# SDRAM.net
KiCad netlist of a schematic drawn in Altium Designer
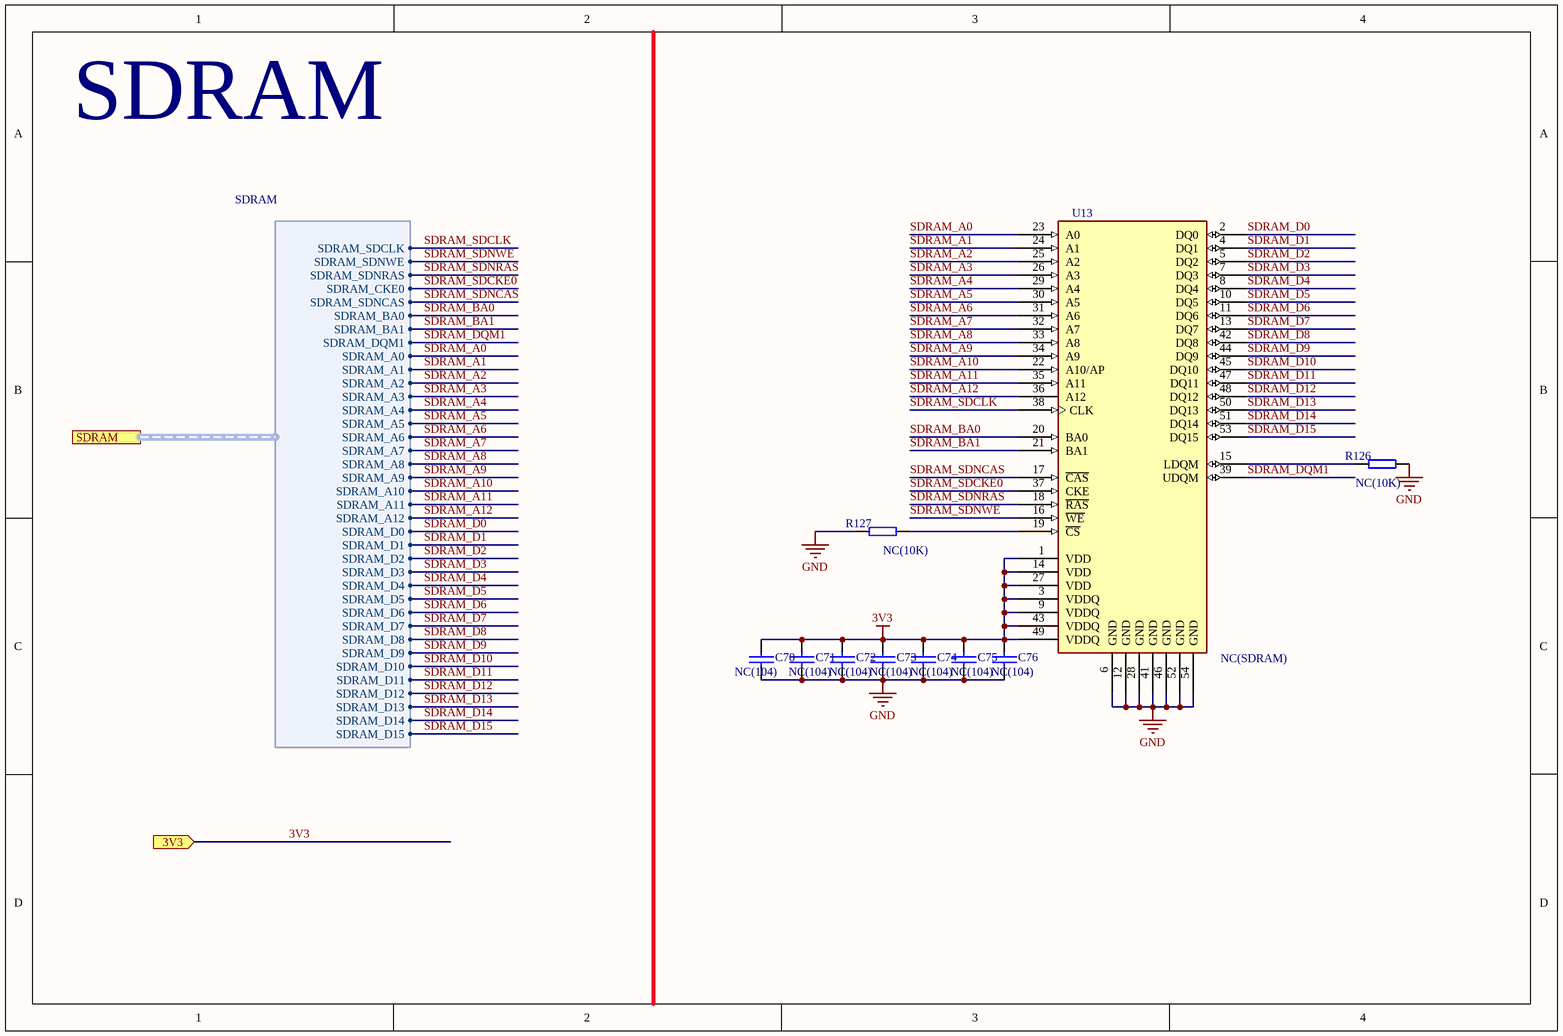
[diagram p0: SDRAM.SchDoc]

(export (version "E")
  (design (tool "Eeschema 10.0.6"))
  (components
    (comp (ref "C70")
      (value "NC(104)")
      (footprint "0402_C")
      (description "Capacitor")
      (libsource (lib "wch_sch_others") (part "CAP"))
    )
    (comp (ref "C71")
      (value "NC(104)")
      (footprint "0402_C")
      (description "Capacitor")
      (libsource (lib "wch_sch_others") (part "CAP"))
    )
    (comp (ref "C72")
      (value "NC(104)")
      (footprint "0402_C")
      (description "Capacitor")
      (libsource (lib "wch_sch_others") (part "CAP"))
    )
    (comp (ref "C73")
      (value "NC(104)")
      (footprint "0402_C")
      (description "Capacitor")
      (libsource (lib "wch_sch_others") (part "CAP"))
    )
    (comp (ref "C74")
      (value "NC(104)")
      (footprint "0402_C")
      (description "Capacitor")
      (libsource (lib "wch_sch_others") (part "CAP"))
    )
    (comp (ref "C75")
      (value "NC(104)")
      (footprint "0402_C")
      (description "Capacitor")
      (libsource (lib "wch_sch_others") (part "CAP"))
    )
    (comp (ref "C76")
      (value "NC(104)")
      (footprint "0402_C")
      (description "Capacitor")
      (libsource (lib "wch_sch_others") (part "CAP"))
    )
    (comp (ref "R126") (value "NC(10K)") (footprint "0402") (libsource (lib "*") (part "RES")))
    (comp (ref "R127") (value "NC(10K)") (footprint "0402") (libsource (lib "*") (part "RES")))
    (comp (ref "U13") (value "NC(SDRAM)") (libsource (lib "wch_sch_others") (part "W9825G6KH-6")))
  )
  (nets
    (net (code "2") (name "/SDRAM_A0") (class "Default")
      (node (ref "U13") (pin "23") (pinfunction "A0_23") (pintype "input"))
    )
    (net (code "3") (name "/SDRAM_A1") (class "Default")
      (node (ref "U13") (pin "24") (pinfunction "A1_24") (pintype "input"))
    )
    (net (code "4") (name "/SDRAM_A2") (class "Default")
      (node (ref "U13") (pin "25") (pinfunction "A2_25") (pintype "input"))
    )
    (net (code "5") (name "/SDRAM_A3") (class "Default")
      (node (ref "U13") (pin "26") (pinfunction "A3_26") (pintype "input"))
    )
    (net (code "6") (name "/SDRAM_A4") (class "Default")
      (node (ref "U13") (pin "29") (pinfunction "A4_29") (pintype "input"))
    )
    (net (code "7") (name "/SDRAM_A5") (class "Default")
      (node (ref "U13") (pin "30") (pinfunction "A5_30") (pintype "input"))
    )
    (net (code "8") (name "/SDRAM_A6") (class "Default")
      (node (ref "U13") (pin "31") (pinfunction "A6_31") (pintype "input"))
    )
    (net (code "9") (name "/SDRAM_A7") (class "Default")
      (node (ref "U13") (pin "32") (pinfunction "A7_32") (pintype "input"))
    )
    (net (code "10") (name "/SDRAM_A8") (class "Default")
      (node (ref "U13") (pin "33") (pinfunction "A8_33") (pintype "input"))
    )
    (net (code "11") (name "/SDRAM_A9") (class "Default")
      (node (ref "U13") (pin "34") (pinfunction "A9_34") (pintype "input"))
    )
    (net (code "12") (name "/SDRAM_A10") (class "Default")
      (node (ref "U13") (pin "22") (pinfunction "A10/AP_22") (pintype "input"))
    )
    (net (code "13") (name "/SDRAM_A11") (class "Default")
      (node (ref "U13") (pin "35") (pinfunction "A11_35") (pintype "input"))
    )
    (net (code "14") (name "/SDRAM_A12") (class "Default")
      (node (ref "U13") (pin "36") (pinfunction "A12_36") (pintype "passive"))
    )
    (net (code "15") (name "/SDRAM_BA0") (class "Default")
      (node (ref "U13") (pin "20") (pinfunction "BA0_20") (pintype "input"))
    )
    (net (code "16") (name "/SDRAM_BA1") (class "Default")
      (node (ref "U13") (pin "21") (pinfunction "BA1_21") (pintype "input"))
    )
    (net (code "17") (name "/SDRAM_D0") (class "Default")
      (node (ref "U13") (pin "2") (pinfunction "DQ0_2") (pintype "bidirectional"))
    )
    (net (code "18") (name "/SDRAM_D1") (class "Default")
      (node (ref "U13") (pin "4") (pinfunction "DQ1_4") (pintype "bidirectional"))
    )
    (net (code "19") (name "/SDRAM_D2") (class "Default")
      (node (ref "U13") (pin "5") (pinfunction "DQ2_5") (pintype "bidirectional"))
    )
    (net (code "20") (name "/SDRAM_D3") (class "Default")
      (node (ref "U13") (pin "7") (pinfunction "DQ3_7") (pintype "bidirectional"))
    )
    (net (code "21") (name "/SDRAM_D4") (class "Default")
      (node (ref "U13") (pin "8") (pinfunction "DQ4_8") (pintype "bidirectional"))
    )
    (net (code "22") (name "/SDRAM_D5") (class "Default")
      (node (ref "U13") (pin "10") (pinfunction "DQ5_10") (pintype "bidirectional"))
    )
    (net (code "23") (name "/SDRAM_D6") (class "Default")
      (node (ref "U13") (pin "11") (pinfunction "DQ6_11") (pintype "bidirectional"))
    )
    (net (code "24") (name "/SDRAM_D7") (class "Default")
      (node (ref "U13") (pin "13") (pinfunction "DQ7_13") (pintype "bidirectional"))
    )
    (net (code "25") (name "/SDRAM_D8") (class "Default")
      (node (ref "U13") (pin "42") (pinfunction "DQ8_42") (pintype "bidirectional"))
    )
    (net (code "26") (name "/SDRAM_D9") (class "Default")
      (node (ref "U13") (pin "44") (pinfunction "DQ9_44") (pintype "bidirectional"))
    )
    (net (code "27") (name "/SDRAM_D10") (class "Default")
      (node (ref "U13") (pin "45") (pinfunction "DQ10_45") (pintype "bidirectional"))
    )
    (net (code "28") (name "/SDRAM_D11") (class "Default")
      (node (ref "U13") (pin "47") (pinfunction "DQ11_47") (pintype "bidirectional"))
    )
    (net (code "29") (name "/SDRAM_D12") (class "Default")
      (node (ref "U13") (pin "48") (pinfunction "DQ12_48") (pintype "bidirectional"))
    )
    (net (code "30") (name "/SDRAM_D13") (class "Default")
      (node (ref "U13") (pin "50") (pinfunction "DQ13_50") (pintype "bidirectional"))
    )
    (net (code "31") (name "/SDRAM_D14") (class "Default")
      (node (ref "U13") (pin "51") (pinfunction "DQ14_51") (pintype "bidirectional"))
    )
    (net (code "32") (name "/SDRAM_D15") (class "Default")
      (node (ref "U13") (pin "53") (pinfunction "DQ15_53") (pintype "bidirectional"))
    )
    (net (code "33") (name "/SDRAM_DQM1") (class "Default")
      (node (ref "U13") (pin "39") (pinfunction "UDQM_39") (pintype "bidirectional"))
    )
    (net (code "34") (name "/SDRAM_SDCKE0") (class "Default")
      (node (ref "U13") (pin "37") (pinfunction "CKE_37") (pintype "input"))
    )
    (net (code "35") (name "/SDRAM_SDCLK") (class "Default")
      (node (ref "U13") (pin "38") (pinfunction "CLK_38") (pintype "input"))
    )
    (net (code "36") (name "/SDRAM_SDNCAS") (class "Default")
      (node (ref "U13") (pin "17") (pinfunction "~{CAS}_17") (pintype "input"))
    )
    (net (code "37") (name "/SDRAM_SDNRAS") (class "Default")
      (node (ref "U13") (pin "18") (pinfunction "~{RAS}_18") (pintype "input"))
    )
    (net (code "38") (name "/SDRAM_SDNWE") (class "Default")
      (node (ref "U13") (pin "16") (pinfunction "~{WE}_16") (pintype "input"))
    )
    (net (code "40") (name "3V3") (class "Default")
      (node (ref "C70") (pin "2") (pinfunction "2_2") (pintype "passive"))
      (node (ref "C71") (pin "2") (pinfunction "2_2") (pintype "passive"))
      (node (ref "C72") (pin "2") (pinfunction "2_2") (pintype "passive"))
      (node (ref "C73") (pin "2") (pinfunction "2_2") (pintype "passive"))
      (node (ref "C74") (pin "2") (pinfunction "2_2") (pintype "passive"))
      (node (ref "C75") (pin "2") (pinfunction "2_2") (pintype "passive"))
      (node (ref "C76") (pin "2") (pinfunction "2_2") (pintype "passive"))
      (node (ref "U13") (pin "1") (pinfunction "VDD_1") (pintype "power_in"))
      (node (ref "U13") (pin "14") (pinfunction "VDD_14") (pintype "power_in"))
      (node (ref "U13") (pin "27") (pinfunction "VDD_27") (pintype "power_in"))
      (node (ref "U13") (pin "3") (pinfunction "VDDQ_3") (pintype "power_in"))
      (node (ref "U13") (pin "43") (pinfunction "VDDQ_43") (pintype "power_in"))
      (node (ref "U13") (pin "49") (pinfunction "VDDQ_49") (pintype "power_in"))
      (node (ref "U13") (pin "9") (pinfunction "VDDQ_9") (pintype "power_in"))
    )
    (net (code "41") (name "GND") (class "Default")
      (node (ref "C70") (pin "1") (pinfunction "1_1") (pintype "passive"))
      (node (ref "C71") (pin "1") (pinfunction "1_1") (pintype "passive"))
      (node (ref "C72") (pin "1") (pinfunction "1_1") (pintype "passive"))
      (node (ref "C73") (pin "1") (pinfunction "1_1") (pintype "passive"))
      (node (ref "C74") (pin "1") (pinfunction "1_1") (pintype "passive"))
      (node (ref "C75") (pin "1") (pinfunction "1_1") (pintype "passive"))
      (node (ref "C76") (pin "1") (pinfunction "1_1") (pintype "passive"))
      (node (ref "R126") (pin "1") (pintype "passive"))
      (node (ref "R127") (pin "2") (pintype "passive"))
      (node (ref "U13") (pin "12") (pinfunction "GND_12") (pintype "power_in"))
      (node (ref "U13") (pin "28") (pinfunction "GND_28") (pintype "power_in"))
      (node (ref "U13") (pin "41") (pinfunction "GND_41") (pintype "power_in"))
      (node (ref "U13") (pin "46") (pinfunction "GND_46") (pintype "power_in"))
      (node (ref "U13") (pin "52") (pinfunction "GND_52") (pintype "power_in"))
      (node (ref "U13") (pin "54") (pinfunction "GND_54") (pintype "power_in"))
      (node (ref "U13") (pin "6") (pinfunction "GND_6") (pintype "power_in"))
    )
    (net (code "42") (name "Net-(U13-LDQM)") (class "Default")
      (node (ref "R126") (pin "2") (pintype "passive"))
      (node (ref "U13") (pin "15") (pinfunction "LDQM_15") (pintype "bidirectional"))
    )
    (net (code "43") (name "Net-(U13-~{CS})") (class "Default")
      (node (ref "R127") (pin "1") (pintype "passive"))
      (node (ref "U13") (pin "19") (pinfunction "~{CS}_19") (pintype "input"))
    )
  )
)
